# 2LD-24-mk-1_0_0.net
KiCad netlist of a schematic drawn in EAGLE
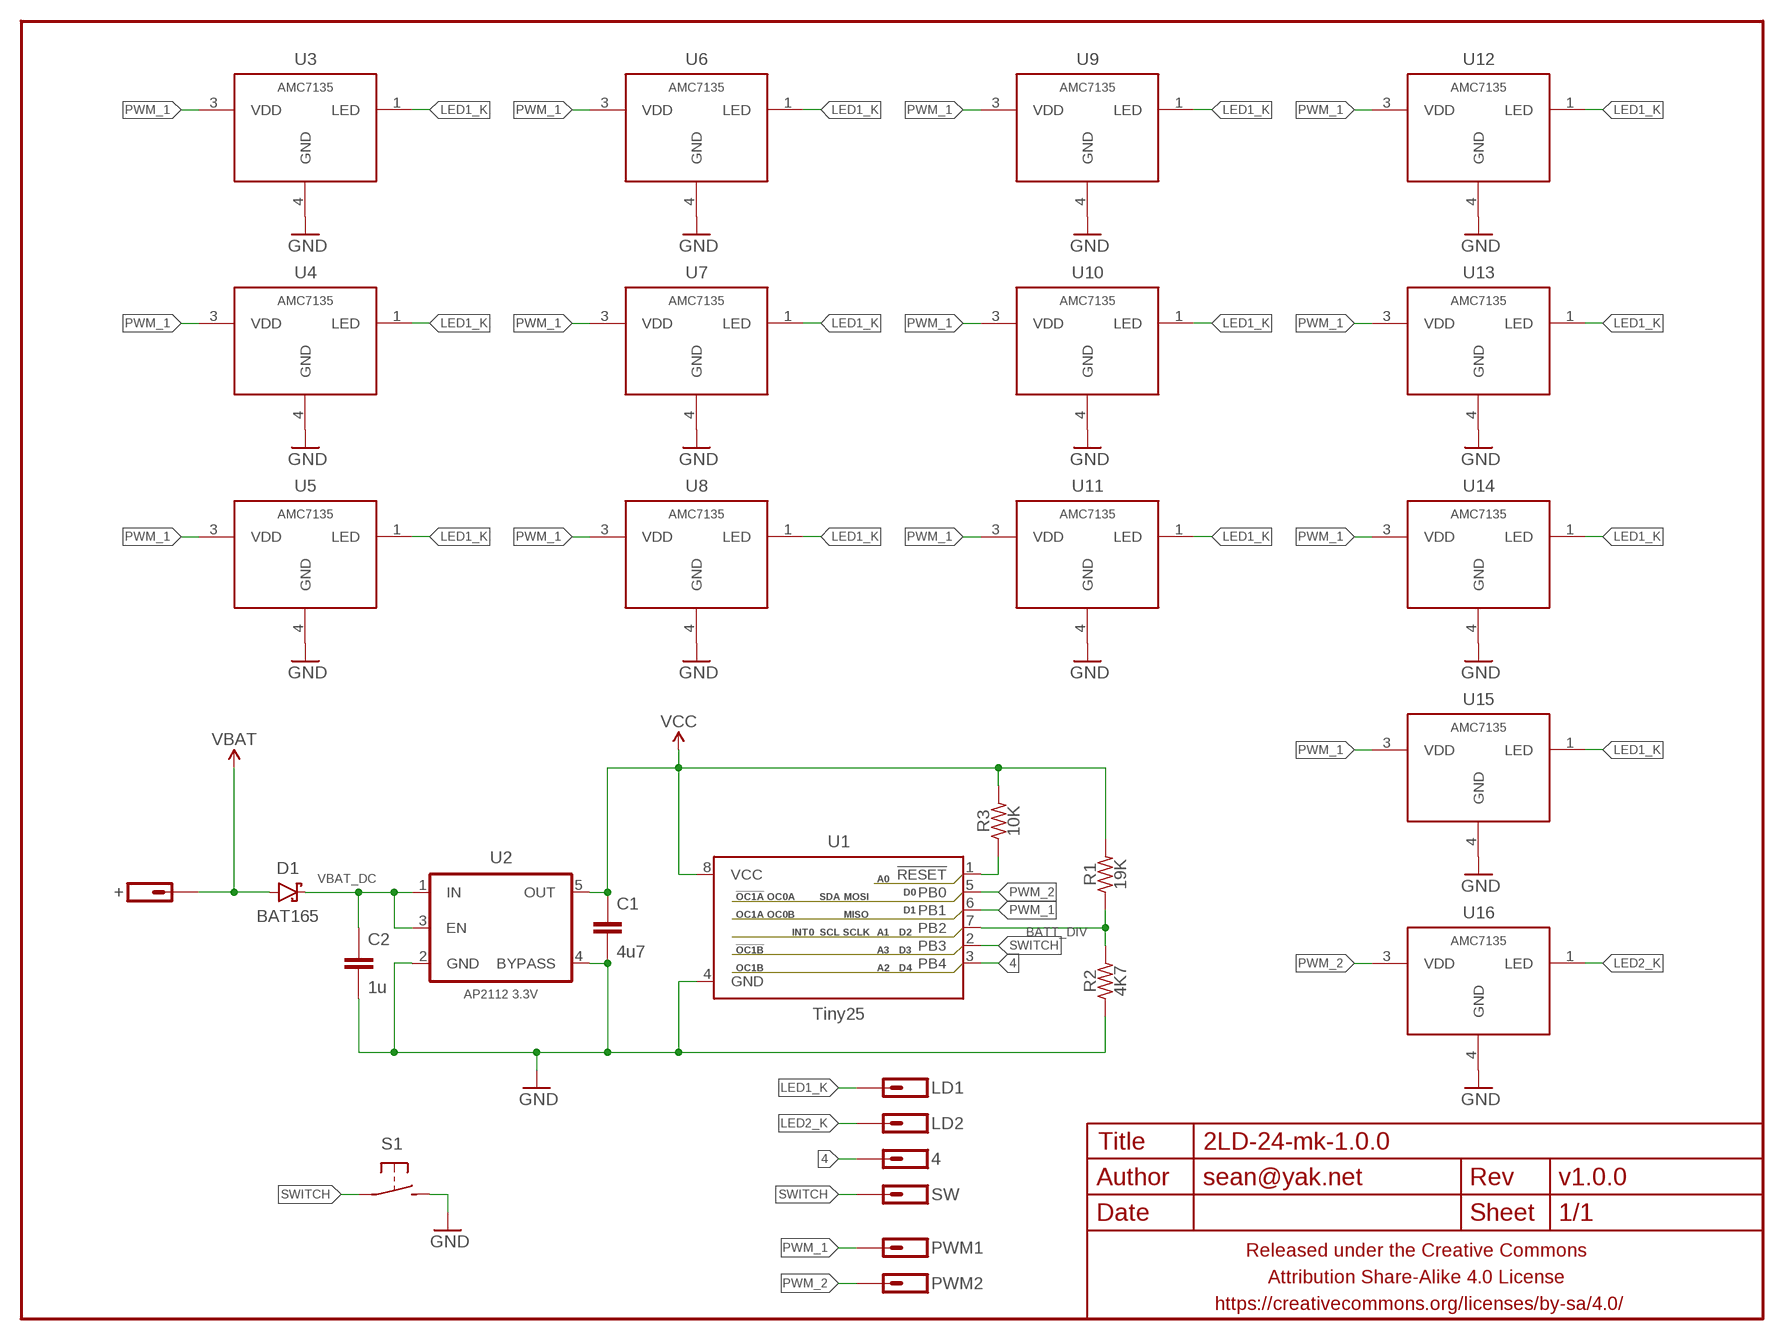
[diagram p0: schematic, sheet 1]

(export (version "E")
  (design (tool "Eeschema 10.0.6"))
  (components
    (comp (ref "+")
      (value "M01PTH-1MM-CIR-NS")
      (footprint "eagle-import:1X01-1MM-CIR-NS")
      (libsource (lib "eagle-import") (part "M01PTH-1MM-CIR-NS"))
    )
    (comp (ref "4")
      (value "M01SMD-0.8MM-DIA-NS")
      (footprint "eagle-import:1X01-SMD-0.8MM-DIA-NS")
      (libsource (lib "eagle-import") (part "M01SMD-0.8MM-DIA-NS"))
    )
    (comp (ref "C1")
      (value "4u7")
      (footprint "eagle-import:C0603-TIGHTER")
      (libsource (lib "eagle-import") (part "CAPACITOR-CERAMICC0603-TIGHTER"))
    )
    (comp (ref "C2")
      (value "1u")
      (footprint "eagle-import:C0603-TIGHTER")
      (libsource (lib "eagle-import") (part "CAPACITOR-CERAMICC0603-TIGHTER"))
    )
    (comp (ref "D1")
      (value "BAT165")
      (footprint "eagle-import:SOD323-SCHOTTKY")
      (libsource (lib "eagle-import") (part "DIODE-SCHOTTKYSOD323"))
    )
    (comp (ref "FRAME1")
      (value "FRAME-LETTERNO_PACKAGE")
      (footprint "eagle-import:DUMMY")
      (fields (field (name "DESIGNER") "sean@yak.net") (field (name "VERSION") "v1.0.0"))
      (libsource (lib "eagle-import") (part "FRAME-LETTERNO_PACKAGE"))
    )
    (comp (ref "LD1")
      (value "M01PTH-1MM-CIR-NS")
      (footprint "eagle-import:1X01-1MM-CIR-NS")
      (libsource (lib "eagle-import") (part "M01PTH-1MM-CIR-NS"))
    )
    (comp (ref "LD2")
      (value "M01PTH-0.8MM-CIR")
      (footprint "eagle-import:1X01-0.8MM-CIR")
      (libsource (lib "eagle-import") (part "M01PTH-0.8MM-CIR"))
    )
    (comp (ref "PWM1")
      (value "M01SMD-0.8MM-DIA-NS")
      (footprint "eagle-import:1X01-SMD-0.8MM-DIA-NS")
      (libsource (lib "eagle-import") (part "M01SMD-0.8MM-DIA-NS"))
    )
    (comp (ref "PWM2")
      (value "M01SMD-0.8MM-DIA-NS")
      (footprint "eagle-import:1X01-SMD-0.8MM-DIA-NS")
      (libsource (lib "eagle-import") (part "M01SMD-0.8MM-DIA-NS"))
    )
    (comp (ref "R1")
      (value "19K")
      (footprint "eagle-import:R0603-TIGHTER")
      (libsource (lib "eagle-import") (part "RESISTORR0603-TIGHTER"))
    )
    (comp (ref "R2")
      (value "4K7")
      (footprint "eagle-import:R0603-TIGHTER")
      (libsource (lib "eagle-import") (part "RESISTORR0603-TIGHTER"))
    )
    (comp (ref "R3")
      (value "10K")
      (footprint "eagle-import:R0603-TIGHTER")
      (libsource (lib "eagle-import") (part "RESISTORR0603-TIGHTER"))
    )
    (comp (ref "S1")
      (value "SPST-NO-TACT3MM-RA-SMALLER")
      (footprint "eagle-import:TACTILE-PTH-SIDE-SMALLER")
      (libsource (lib "eagle-import") (part "SPST-NO-TACT3MM-RA-SMALLER"))
    )
    (comp (ref "SW")
      (value "M01SMD-0.8MM-DIA-NS")
      (footprint "eagle-import:1X01-SMD-0.8MM-DIA-NS")
      (libsource (lib "eagle-import") (part "M01SMD-0.8MM-DIA-NS"))
    )
    (comp (ref "U1")
      (value "Tiny25")
      (footprint "eagle-import:SO08-NARROWER")
      (libsource (lib "eagle-import") (part "ATTINY13SOIC-NARROWPADS"))
    )
    (comp (ref "U2")
      (value "AP2112 3.3V")
      (footprint "eagle-import:SOT23-5-SLIM")
      (libsource (lib "eagle-import") (part "V_REG_SOT-23-5APA2112-SLIM"))
    )
    (comp (ref "U3")
      (value "AMC7135")
      (footprint "eagle-import:SOT89-NOTHERM-ROUNDED-LESS")
      (libsource (lib "eagle-import") (part "AMC7135SOT-89-NOTHERM-ROUNDED-LESS"))
    )
    (comp (ref "U4")
      (value "AMC7135")
      (footprint "eagle-import:SOT89-NOTHERM-ROUNDED-LESS")
      (libsource (lib "eagle-import") (part "AMC7135SOT-89-NOTHERM-ROUNDED-LESS"))
    )
    (comp (ref "U5")
      (value "AMC7135")
      (footprint "eagle-import:SOT89-NOTHERM-ROUNDED-LESS")
      (libsource (lib "eagle-import") (part "AMC7135SOT-89-NOTHERM-ROUNDED-LESS"))
    )
    (comp (ref "U6")
      (value "AMC7135")
      (footprint "eagle-import:SOT89-NOTHERM-ROUNDED-LESS")
      (libsource (lib "eagle-import") (part "AMC7135SOT-89-NOTHERM-ROUNDED-LESS"))
    )
    (comp (ref "U7")
      (value "AMC7135")
      (footprint "eagle-import:SOT89-NOTHERM-ROUNDED-LESS")
      (libsource (lib "eagle-import") (part "AMC7135SOT-89-NOTHERM-ROUNDED-LESS"))
    )
    (comp (ref "U8")
      (value "AMC7135")
      (footprint "eagle-import:SOT89-NOTHERM-ROUNDED-LESS")
      (libsource (lib "eagle-import") (part "AMC7135SOT-89-NOTHERM-ROUNDED-LESS"))
    )
    (comp (ref "U9")
      (value "AMC7135")
      (footprint "eagle-import:SOT89-NOTHERM-ROUNDED-LESS")
      (libsource (lib "eagle-import") (part "AMC7135SOT-89-NOTHERM-ROUNDED-LESS"))
    )
    (comp (ref "U10")
      (value "AMC7135")
      (footprint "eagle-import:SOT89-NOTHERM-ROUNDED-LESS")
      (libsource (lib "eagle-import") (part "AMC7135SOT-89-NOTHERM-ROUNDED-LESS"))
    )
    (comp (ref "U11")
      (value "AMC7135")
      (footprint "eagle-import:SOT89-NOTHERM-ROUNDED-LESS")
      (libsource (lib "eagle-import") (part "AMC7135SOT-89-NOTHERM-ROUNDED-LESS"))
    )
    (comp (ref "U12")
      (value "AMC7135")
      (footprint "eagle-import:SOT89-NOTHERM-ROUNDED-LESS")
      (libsource (lib "eagle-import") (part "AMC7135SOT-89-NOTHERM-ROUNDED-LESS"))
    )
    (comp (ref "U13")
      (value "AMC7135")
      (footprint "eagle-import:SOT89-NOTHERM-ROUNDED-LESS")
      (libsource (lib "eagle-import") (part "AMC7135SOT-89-NOTHERM-ROUNDED-LESS"))
    )
    (comp (ref "U14")
      (value "AMC7135")
      (footprint "eagle-import:SOT89-NOTHERM-ROUNDED-LESS")
      (libsource (lib "eagle-import") (part "AMC7135SOT-89-NOTHERM-ROUNDED-LESS"))
    )
    (comp (ref "U15")
      (value "AMC7135")
      (footprint "eagle-import:SOT89-NOTHERM-ROUNDED-LESS")
      (libsource (lib "eagle-import") (part "AMC7135SOT-89-NOTHERM-ROUNDED-LESS"))
    )
    (comp (ref "U16")
      (value "AMC7135")
      (footprint "eagle-import:SOT89-NOTHERM-ROUNDED-LESS")
      (libsource (lib "eagle-import") (part "AMC7135SOT-89-NOTHERM-ROUNDED-LESS"))
    )
  )
  (nets
    (net (code "1") (name "/BATT_DIV") (class "Default")
      (node (ref "R1") (pin "1") (pinfunction "1_1") (pintype "passive"))
      (node (ref "R2") (pin "2") (pinfunction "2_2") (pintype "passive"))
      (node (ref "U1") (pin "7") (pinfunction "PB2_7") (pintype "bidirectional"))
    )
    (net (code "2") (name "/VBAT_DC") (class "Default")
      (node (ref "C2") (pin "1") (pinfunction "1_1") (pintype "passive"))
      (node (ref "D1") (pin "C") (pinfunction "C_C") (pintype "passive"))
      (node (ref "U2") (pin "1") (pinfunction "IN_1") (pintype "input"))
      (node (ref "U2") (pin "3") (pinfunction "EN_3") (pintype "input"))
    )
    (net (code "3") (name "4") (class "Default")
      (node (ref "4") (pin "P$1") (pinfunction "1_P$1") (pintype "passive"))
      (node (ref "U1") (pin "3") (pinfunction "PB4_3") (pintype "bidirectional"))
    )
    (net (code "4") (name "GND") (class "Default")
      (node (ref "C1") (pin "2") (pinfunction "2_2") (pintype "passive"))
      (node (ref "C2") (pin "2") (pinfunction "2_2") (pintype "passive"))
      (node (ref "R2") (pin "1") (pinfunction "1_1") (pintype "passive"))
      (node (ref "S1") (pin "2") (pinfunction "2_2") (pintype "passive"))
      (node (ref "U1") (pin "4") (pinfunction "GND_4") (pintype "bidirectional"))
      (node (ref "U10") (pin "4") (pinfunction "GND_4") (pintype "bidirectional"))
      (node (ref "U11") (pin "4") (pinfunction "GND_4") (pintype "bidirectional"))
      (node (ref "U12") (pin "4") (pinfunction "GND_4") (pintype "bidirectional"))
      (node (ref "U13") (pin "4") (pinfunction "GND_4") (pintype "bidirectional"))
      (node (ref "U14") (pin "4") (pinfunction "GND_4") (pintype "bidirectional"))
      (node (ref "U15") (pin "4") (pinfunction "GND_4") (pintype "bidirectional"))
      (node (ref "U16") (pin "4") (pinfunction "GND_4") (pintype "bidirectional"))
      (node (ref "U2") (pin "2") (pinfunction "GND_2") (pintype "input"))
      (node (ref "U2") (pin "4") (pinfunction "BYPASS_4") (pintype "input"))
      (node (ref "U3") (pin "4") (pinfunction "GND_4") (pintype "bidirectional"))
      (node (ref "U4") (pin "4") (pinfunction "GND_4") (pintype "bidirectional"))
      (node (ref "U5") (pin "4") (pinfunction "GND_4") (pintype "bidirectional"))
      (node (ref "U6") (pin "4") (pinfunction "GND_4") (pintype "bidirectional"))
      (node (ref "U7") (pin "4") (pinfunction "GND_4") (pintype "bidirectional"))
      (node (ref "U8") (pin "4") (pinfunction "GND_4") (pintype "bidirectional"))
      (node (ref "U9") (pin "4") (pinfunction "GND_4") (pintype "bidirectional"))
    )
    (net (code "5") (name "LED1_K") (class "Default")
      (node (ref "LD1") (pin "1") (pinfunction "1_1") (pintype "passive"))
      (node (ref "U10") (pin "1") (pinfunction "LED_1") (pintype "bidirectional"))
      (node (ref "U11") (pin "1") (pinfunction "LED_1") (pintype "bidirectional"))
      (node (ref "U12") (pin "1") (pinfunction "LED_1") (pintype "bidirectional"))
      (node (ref "U13") (pin "1") (pinfunction "LED_1") (pintype "bidirectional"))
      (node (ref "U14") (pin "1") (pinfunction "LED_1") (pintype "bidirectional"))
      (node (ref "U15") (pin "1") (pinfunction "LED_1") (pintype "bidirectional"))
      (node (ref "U3") (pin "1") (pinfunction "LED_1") (pintype "bidirectional"))
      (node (ref "U4") (pin "1") (pinfunction "LED_1") (pintype "bidirectional"))
      (node (ref "U5") (pin "1") (pinfunction "LED_1") (pintype "bidirectional"))
      (node (ref "U6") (pin "1") (pinfunction "LED_1") (pintype "bidirectional"))
      (node (ref "U7") (pin "1") (pinfunction "LED_1") (pintype "bidirectional"))
      (node (ref "U8") (pin "1") (pinfunction "LED_1") (pintype "bidirectional"))
      (node (ref "U9") (pin "1") (pinfunction "LED_1") (pintype "bidirectional"))
    )
    (net (code "6") (name "LED2_K") (class "Default")
      (node (ref "LD2") (pin "1") (pinfunction "1_1") (pintype "passive"))
      (node (ref "U16") (pin "1") (pinfunction "LED_1") (pintype "bidirectional"))
    )
    (net (code "7") (name "Net-(U1-~{RESET})") (class "Default")
      (node (ref "R3") (pin "1") (pinfunction "1_1") (pintype "passive"))
      (node (ref "U1") (pin "1") (pinfunction "~{RESET}_1") (pintype "bidirectional"))
    )
    (net (code "8") (name "PWM_1") (class "Default")
      (node (ref "PWM1") (pin "P$1") (pinfunction "1_P$1") (pintype "passive"))
      (node (ref "U1") (pin "6") (pinfunction "PB1_6") (pintype "bidirectional"))
      (node (ref "U10") (pin "3") (pinfunction "VDD_3") (pintype "bidirectional"))
      (node (ref "U11") (pin "3") (pinfunction "VDD_3") (pintype "bidirectional"))
      (node (ref "U12") (pin "3") (pinfunction "VDD_3") (pintype "bidirectional"))
      (node (ref "U13") (pin "3") (pinfunction "VDD_3") (pintype "bidirectional"))
      (node (ref "U14") (pin "3") (pinfunction "VDD_3") (pintype "bidirectional"))
      (node (ref "U15") (pin "3") (pinfunction "VDD_3") (pintype "bidirectional"))
      (node (ref "U3") (pin "3") (pinfunction "VDD_3") (pintype "bidirectional"))
      (node (ref "U4") (pin "3") (pinfunction "VDD_3") (pintype "bidirectional"))
      (node (ref "U5") (pin "3") (pinfunction "VDD_3") (pintype "bidirectional"))
      (node (ref "U6") (pin "3") (pinfunction "VDD_3") (pintype "bidirectional"))
      (node (ref "U7") (pin "3") (pinfunction "VDD_3") (pintype "bidirectional"))
      (node (ref "U8") (pin "3") (pinfunction "VDD_3") (pintype "bidirectional"))
      (node (ref "U9") (pin "3") (pinfunction "VDD_3") (pintype "bidirectional"))
    )
    (net (code "9") (name "PWM_2") (class "Default")
      (node (ref "PWM2") (pin "P$1") (pinfunction "1_P$1") (pintype "passive"))
      (node (ref "U1") (pin "5") (pinfunction "PB0_5") (pintype "bidirectional"))
      (node (ref "U16") (pin "3") (pinfunction "VDD_3") (pintype "bidirectional"))
    )
    (net (code "10") (name "SWITCH") (class "Default")
      (node (ref "S1") (pin "1") (pinfunction "1_1") (pintype "passive"))
      (node (ref "SW") (pin "P$1") (pinfunction "1_P$1") (pintype "passive"))
      (node (ref "U1") (pin "2") (pinfunction "PB3_2") (pintype "bidirectional"))
    )
    (net (code "11") (name "VBAT") (class "Default")
      (node (ref "+") (pin "1") (pinfunction "1_1") (pintype "passive"))
      (node (ref "D1") (pin "A") (pinfunction "A_A") (pintype "passive"))
    )
    (net (code "12") (name "VCC") (class "Default")
      (node (ref "C1") (pin "1") (pinfunction "1_1") (pintype "passive"))
      (node (ref "R1") (pin "2") (pinfunction "2_2") (pintype "passive"))
      (node (ref "R3") (pin "2") (pinfunction "2_2") (pintype "passive"))
      (node (ref "U1") (pin "8") (pinfunction "VCC_8") (pintype "bidirectional"))
      (node (ref "U2") (pin "5") (pinfunction "OUT_5") (pintype "passive"))
    )
  )
)
